# switch-2layer-4.net
KiCad netlist of a schematic drawn in EAGLE
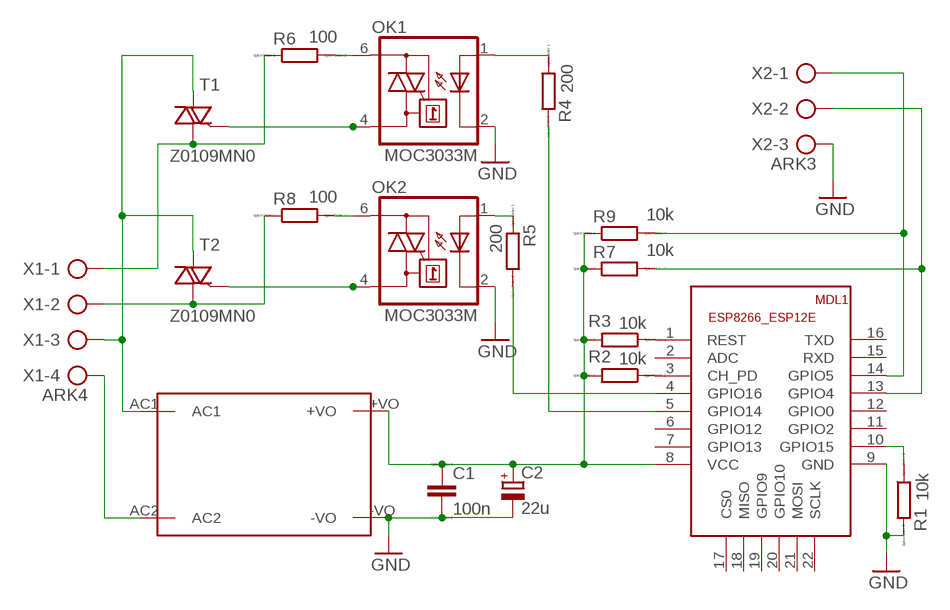
[diagram p0: schematic, sheet 1]

(export (version "E")
  (design (tool "Eeschema 10.0.6"))
  (components
    (comp (ref "C1")
      (value "100n")
      (footprint "eagle-import:C1206")
      (libsource (lib "eagle-import") (part "CC1206"))
    )
    (comp (ref "C2")
      (value "22u")
      (footprint "eagle-import:E2,5-6")
      (libsource (lib "eagle-import") (part "CPOL-EUE2.5-6"))
    )
    (comp (ref "MDL1")
      (value "ESP12-F")
      (footprint "eagle-import:ESP8266-ESP12E")
      (libsource (lib "eagle-import") (part "ESP8266-12EESP8266-ESP12E"))
    )
    (comp (ref "OK1")
      (value "MOC3033M")
      (footprint "eagle-import:DIL06")
      (fields (field (name "MF") "FAIRCHILD SEMICONDUCTOR") (field (name "MPN") "MOC3033-M"))
      (libsource (lib "eagle-import") (part "MOC3033M"))
    )
    (comp (ref "OK2")
      (value "MOC3033M")
      (footprint "eagle-import:DIL06")
      (fields (field (name "MF") "FAIRCHILD SEMICONDUCTOR") (field (name "MPN") "MOC3033-M"))
      (libsource (lib "eagle-import") (part "MOC3033M"))
    )
    (comp (ref "R1")
      (value "10k")
      (footprint "eagle-import:R1206")
      (libsource (lib "eagle-import") (part "RR1206"))
    )
    (comp (ref "R2")
      (value "10k")
      (footprint "eagle-import:R1206")
      (libsource (lib "eagle-import") (part "RR1206"))
    )
    (comp (ref "R3")
      (value "10k")
      (footprint "eagle-import:R1206")
      (libsource (lib "eagle-import") (part "RR1206"))
    )
    (comp (ref "R4")
      (value "200")
      (footprint "eagle-import:R1206")
      (libsource (lib "eagle-import") (part "RR1206"))
    )
    (comp (ref "R5")
      (value "200")
      (footprint "eagle-import:R1206")
      (libsource (lib "eagle-import") (part "RR1206"))
    )
    (comp (ref "R6")
      (value "100")
      (footprint "eagle-import:R1206")
      (libsource (lib "eagle-import") (part "RR1206"))
    )
    (comp (ref "R7")
      (value "10k")
      (footprint "eagle-import:R1206")
      (libsource (lib "eagle-import") (part "RR1206"))
    )
    (comp (ref "R8")
      (value "100")
      (footprint "eagle-import:R1206")
      (libsource (lib "eagle-import") (part "RR1206"))
    )
    (comp (ref "R9")
      (value "10k")
      (footprint "eagle-import:R1206")
      (libsource (lib "eagle-import") (part "RR1206"))
    )
    (comp (ref "T1")
      (value "Z0109MN0")
      (footprint "eagle-import:SOT223")
      (libsource (lib "eagle-import") (part "Z0109MN0"))
    )
    (comp (ref "T2")
      (value "Z0109MN0")
      (footprint "eagle-import:SOT223")
      (libsource (lib "eagle-import") (part "Z0109MN0"))
    )
    (comp (ref "U$1")
      (value "HLK-PM03")
      (footprint "eagle-import:HLK-PM03")
      (libsource (lib "eagle-import") (part "HLK-PM03"))
    )
    (comp (ref "X1")
      (value "ARK4")
      (footprint "eagle-import:AK500_4")
      (libsource (lib "eagle-import") (part "AK500/4"))
    )
    (comp (ref "X2")
      (value "ARK3")
      (footprint "eagle-import:AK500_3")
      (libsource (lib "eagle-import") (part "AK500/3"))
    )
  )
  (nets
    (net (code "1") (name "GND") (class "Default")
      (node (ref "C1") (pin "2") (pinfunction "2_2") (pintype "passive"))
      (node (ref "C2") (pin "-") (pinfunction "-_-") (pintype "passive"))
      (node (ref "MDL1") (pin "9") (pinfunction "GND_9") (pintype "bidirectional"))
      (node (ref "OK1") (pin "2") (pinfunction "C_2") (pintype "passive"))
      (node (ref "OK2") (pin "2") (pinfunction "C_2") (pintype "passive"))
      (node (ref "R1") (pin "2") (pinfunction "2_2") (pintype "passive"))
      (node (ref "U$1") (pin "-VO") (pinfunction "-VO_-VO") (pintype "bidirectional"))
      (node (ref "X2") (pin "3") (pinfunction "KL_3") (pintype "passive"))
    )
    (net (code "2") (name "Net-(MDL1-CH_PD)") (class "Default")
      (node (ref "MDL1") (pin "3") (pinfunction "CH_PD_3") (pintype "bidirectional"))
      (node (ref "R2") (pin "1") (pinfunction "1_1") (pintype "passive"))
    )
    (net (code "3") (name "Net-(MDL1-GPIO4)") (class "Default")
      (node (ref "MDL1") (pin "13") (pinfunction "GPIO4_13") (pintype "bidirectional"))
      (node (ref "R7") (pin "2") (pinfunction "2_2") (pintype "passive"))
      (node (ref "X2") (pin "2") (pinfunction "KL_2") (pintype "passive"))
    )
    (net (code "4") (name "Net-(MDL1-GPIO5)") (class "Default")
      (node (ref "MDL1") (pin "14") (pinfunction "GPIO5_14") (pintype "bidirectional"))
      (node (ref "R9") (pin "2") (pinfunction "2_2") (pintype "passive"))
      (node (ref "X2") (pin "1") (pinfunction "KL_1") (pintype "passive"))
    )
    (net (code "5") (name "Net-(MDL1-GPIO14)") (class "Default")
      (node (ref "MDL1") (pin "5") (pinfunction "GPIO14_5") (pintype "bidirectional"))
      (node (ref "R4") (pin "2") (pinfunction "2_2") (pintype "passive"))
    )
    (net (code "6") (name "Net-(MDL1-GPIO15)") (class "Default")
      (node (ref "MDL1") (pin "10") (pinfunction "GPIO15_10") (pintype "bidirectional"))
      (node (ref "R1") (pin "1") (pinfunction "1_1") (pintype "passive"))
    )
    (net (code "7") (name "Net-(MDL1-GPIO16)") (class "Default")
      (node (ref "MDL1") (pin "4") (pinfunction "GPIO16_4") (pintype "bidirectional"))
      (node (ref "R5") (pin "2") (pinfunction "2_2") (pintype "passive"))
    )
    (net (code "8") (name "Net-(MDL1-REST)") (class "Default")
      (node (ref "MDL1") (pin "1") (pinfunction "REST_1") (pintype "bidirectional"))
      (node (ref "R3") (pin "1") (pinfunction "1_1") (pintype "passive"))
    )
    (net (code "9") (name "Net-(MDL1-VCC)") (class "Default")
      (node (ref "C1") (pin "1") (pinfunction "1_1") (pintype "passive"))
      (node (ref "C2") (pin "+") (pinfunction "+_+") (pintype "passive"))
      (node (ref "MDL1") (pin "8") (pinfunction "VCC_8") (pintype "bidirectional"))
      (node (ref "R2") (pin "2") (pinfunction "2_2") (pintype "passive"))
      (node (ref "R3") (pin "2") (pinfunction "2_2") (pintype "passive"))
      (node (ref "R7") (pin "1") (pinfunction "1_1") (pintype "passive"))
      (node (ref "R9") (pin "1") (pinfunction "1_1") (pintype "passive"))
      (node (ref "U$1") (pin "+VO") (pinfunction "+VO_+VO") (pintype "bidirectional"))
    )
    (net (code "10") (name "Net-(OK1-A)") (class "Default")
      (node (ref "OK1") (pin "1") (pinfunction "A_1") (pintype "passive"))
      (node (ref "R4") (pin "1") (pinfunction "1_1") (pintype "passive"))
    )
    (net (code "11") (name "Net-(OK1-A1)") (class "Default")
      (node (ref "OK1") (pin "4") (pinfunction "A1_4") (pintype "passive"))
      (node (ref "T1") (pin "3") (pinfunction "G_3") (pintype "passive"))
    )
    (net (code "12") (name "Net-(OK1-A2)") (class "Default")
      (node (ref "OK1") (pin "6") (pinfunction "A2_6") (pintype "passive"))
      (node (ref "R6") (pin "2") (pinfunction "2_2") (pintype "passive"))
    )
    (net (code "13") (name "Net-(OK2-A)") (class "Default")
      (node (ref "OK2") (pin "1") (pinfunction "A_1") (pintype "passive"))
      (node (ref "R5") (pin "1") (pinfunction "1_1") (pintype "passive"))
    )
    (net (code "14") (name "Net-(OK2-A1)") (class "Default")
      (node (ref "OK2") (pin "4") (pinfunction "A1_4") (pintype "passive"))
      (node (ref "T2") (pin "3") (pinfunction "G_3") (pintype "passive"))
    )
    (net (code "15") (name "Net-(OK2-A2)") (class "Default")
      (node (ref "OK2") (pin "6") (pinfunction "A2_6") (pintype "passive"))
      (node (ref "R8") (pin "2") (pinfunction "2_2") (pintype "passive"))
    )
    (net (code "16") (name "Net-(T1-LD)") (class "Default")
      (node (ref "T1") (pin "1") (pinfunction "LD_1") (pintype "passive"))
      (node (ref "T2") (pin "1") (pinfunction "LD_1") (pintype "passive"))
      (node (ref "U$1") (pin "AC1") (pinfunction "AC1_AC1") (pintype "bidirectional"))
      (node (ref "X1") (pin "3") (pinfunction "KL_3") (pintype "passive"))
    )
    (net (code "17") (name "Net-(X1A-KL)") (class "Default")
      (node (ref "R6") (pin "1") (pinfunction "1_1") (pintype "passive"))
      (node (ref "T1") (pin "2") (pinfunction "CM_2") (pintype "passive"))
      (node (ref "T1") (pin "4") (pinfunction "CM_4") (pintype "passive"))
      (node (ref "X1") (pin "1") (pinfunction "KL_1") (pintype "passive"))
    )
    (net (code "18") (name "Net-(X1B-KL)") (class "Default")
      (node (ref "R8") (pin "1") (pinfunction "1_1") (pintype "passive"))
      (node (ref "T2") (pin "2") (pinfunction "CM_2") (pintype "passive"))
      (node (ref "T2") (pin "4") (pinfunction "CM_4") (pintype "passive"))
      (node (ref "X1") (pin "2") (pinfunction "KL_2") (pintype "passive"))
    )
    (net (code "19") (name "Net-(X1D-KL)") (class "Default")
      (node (ref "U$1") (pin "AC2") (pinfunction "AC2_AC2") (pintype "bidirectional"))
      (node (ref "X1") (pin "4") (pinfunction "KL_4") (pintype "passive"))
    )
    (net (code "20") (name "unconnected-(MDL1-ADC-Pad2)") (class "Default")
      (node (ref "MDL1") (pin "2") (pinfunction "ADC_2") (pintype "bidirectional"))
    )
    (net (code "21") (name "unconnected-(MDL1-CS0-Pad17)") (class "Default")
      (node (ref "MDL1") (pin "17") (pinfunction "CS0_17") (pintype "bidirectional"))
    )
    (net (code "22") (name "unconnected-(MDL1-GPIO0-Pad12)") (class "Default")
      (node (ref "MDL1") (pin "12") (pinfunction "GPIO0_12") (pintype "bidirectional"))
    )
    (net (code "23") (name "unconnected-(MDL1-GPIO2-Pad11)") (class "Default")
      (node (ref "MDL1") (pin "11") (pinfunction "GPIO2_11") (pintype "bidirectional"))
    )
    (net (code "24") (name "unconnected-(MDL1-GPIO9-Pad19)") (class "Default")
      (node (ref "MDL1") (pin "19") (pinfunction "GPIO9_19") (pintype "bidirectional"))
    )
    (net (code "25") (name "unconnected-(MDL1-GPIO10-Pad20)") (class "Default")
      (node (ref "MDL1") (pin "20") (pinfunction "GPIO10_20") (pintype "bidirectional"))
    )
    (net (code "26") (name "unconnected-(MDL1-GPIO12-Pad6)") (class "Default")
      (node (ref "MDL1") (pin "6") (pinfunction "GPIO12_6") (pintype "bidirectional"))
    )
    (net (code "27") (name "unconnected-(MDL1-GPIO13-Pad7)") (class "Default")
      (node (ref "MDL1") (pin "7") (pinfunction "GPIO13_7") (pintype "bidirectional"))
    )
    (net (code "28") (name "unconnected-(MDL1-MISO-Pad18)") (class "Default")
      (node (ref "MDL1") (pin "18") (pinfunction "MISO_18") (pintype "bidirectional"))
    )
    (net (code "29") (name "unconnected-(MDL1-MOSI-Pad21)") (class "Default")
      (node (ref "MDL1") (pin "21") (pinfunction "MOSI_21") (pintype "bidirectional"))
    )
    (net (code "30") (name "unconnected-(MDL1-RXD-Pad15)") (class "Default")
      (node (ref "MDL1") (pin "15") (pinfunction "RXD_15") (pintype "bidirectional"))
    )
    (net (code "31") (name "unconnected-(MDL1-SCLK-Pad22)") (class "Default")
      (node (ref "MDL1") (pin "22") (pinfunction "SCLK_22") (pintype "bidirectional"))
    )
    (net (code "32") (name "unconnected-(MDL1-TXD-Pad16)") (class "Default")
      (node (ref "MDL1") (pin "16") (pinfunction "TXD_16") (pintype "bidirectional"))
    )
  )
)
